# LcsNodes-Extension-4x4-Occ-Detect-B_02_0.net
KiCad netlist of a schematic drawn in EasyEDA
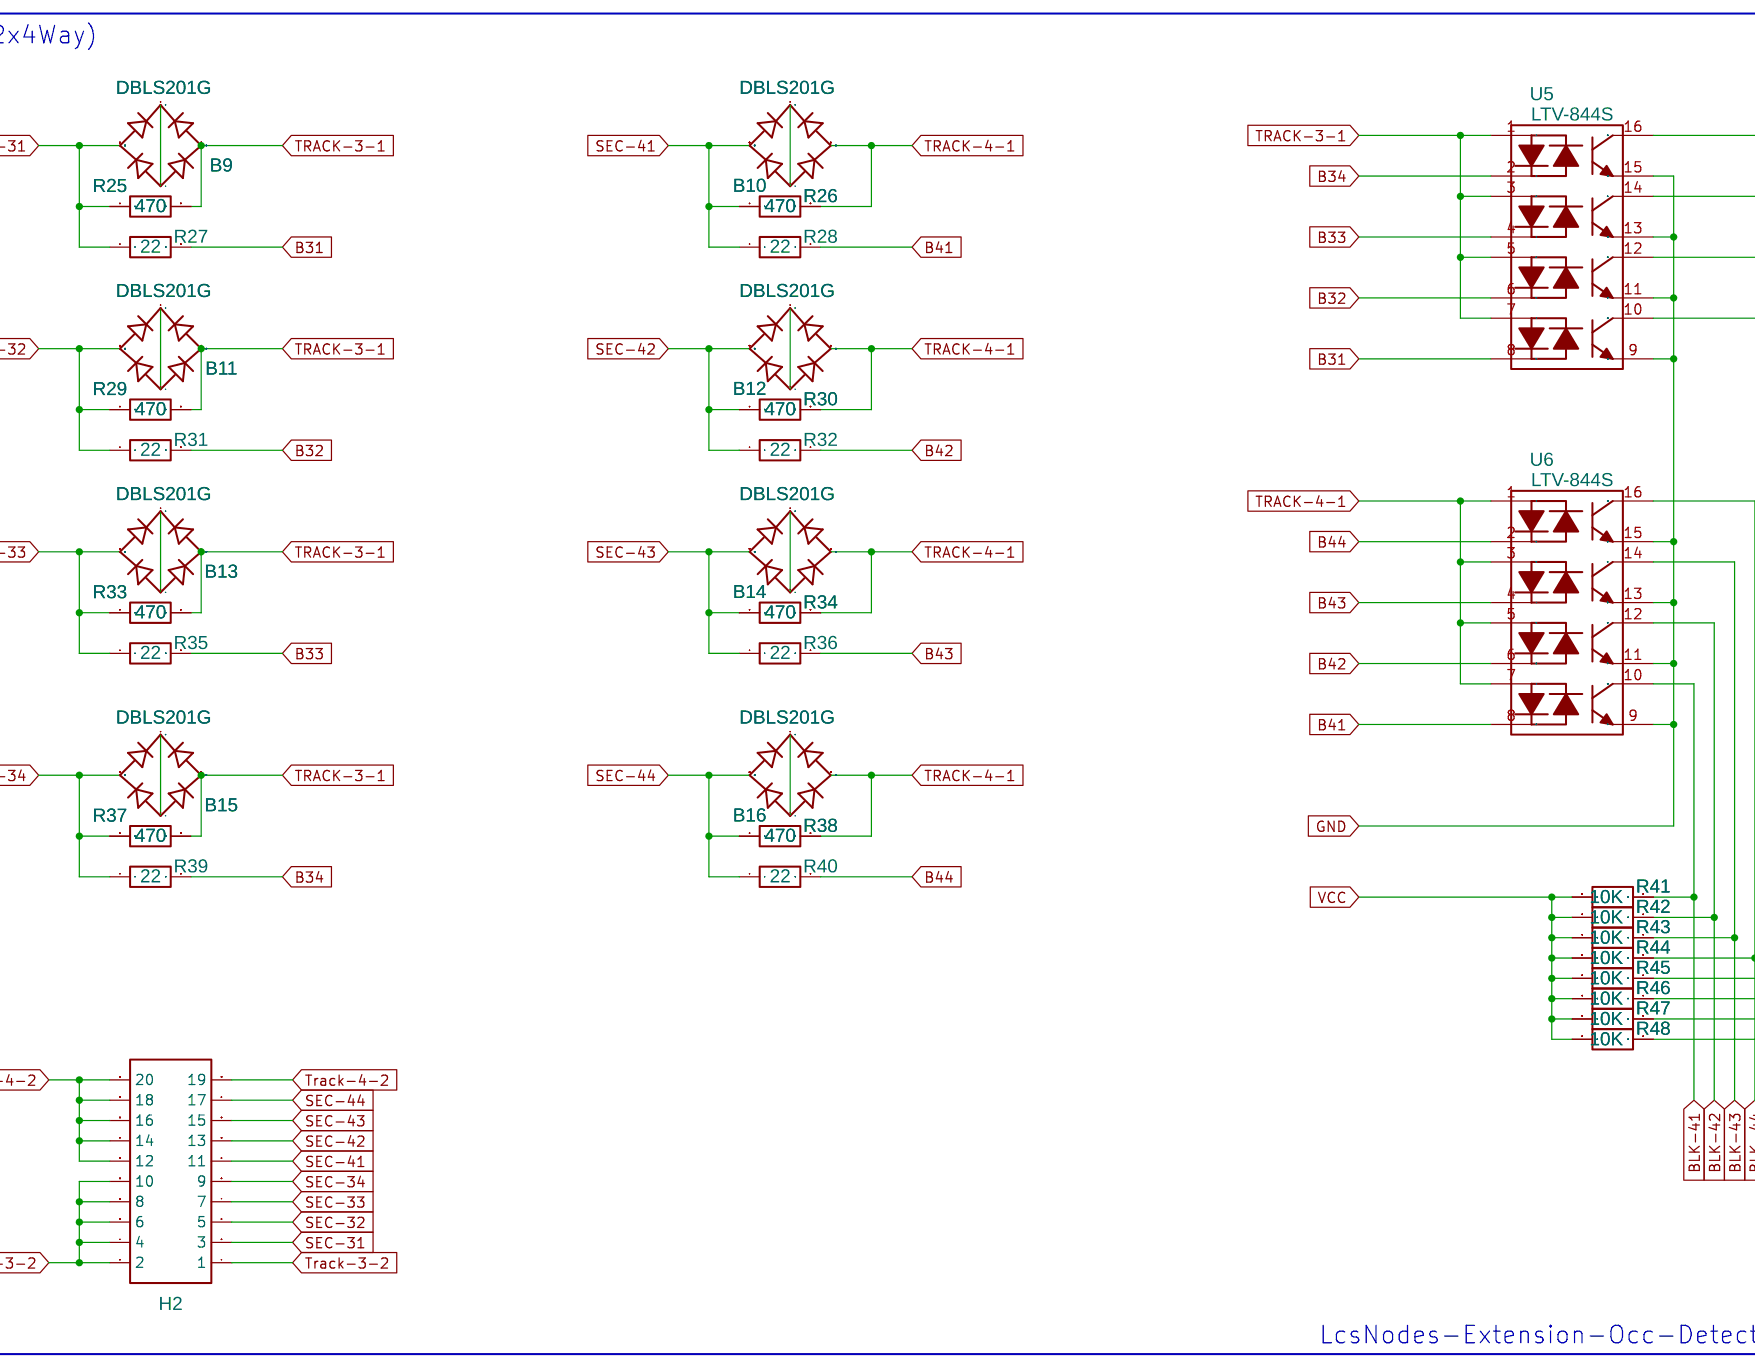
[diagram p0: Sensor-Array-2]
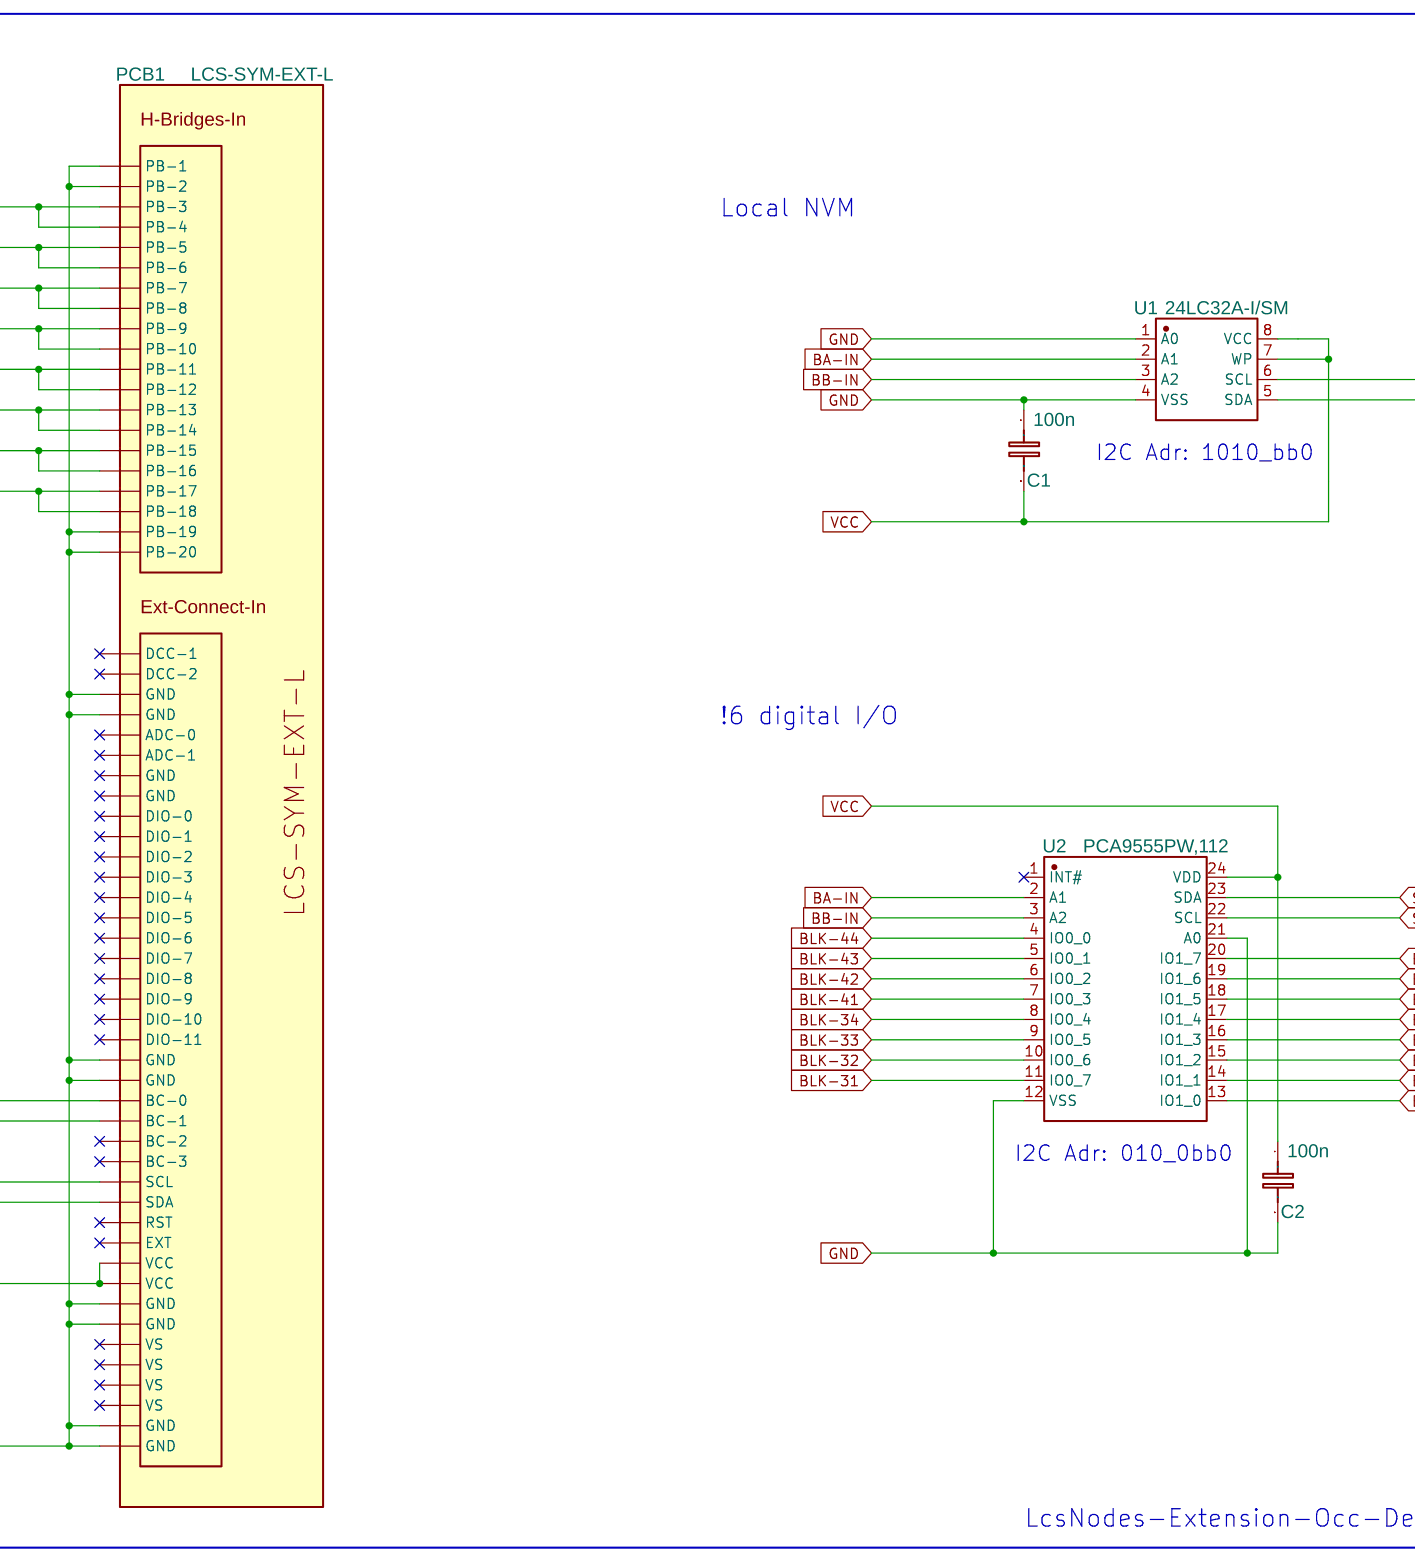
[diagram p1: Connector-and-Logic]
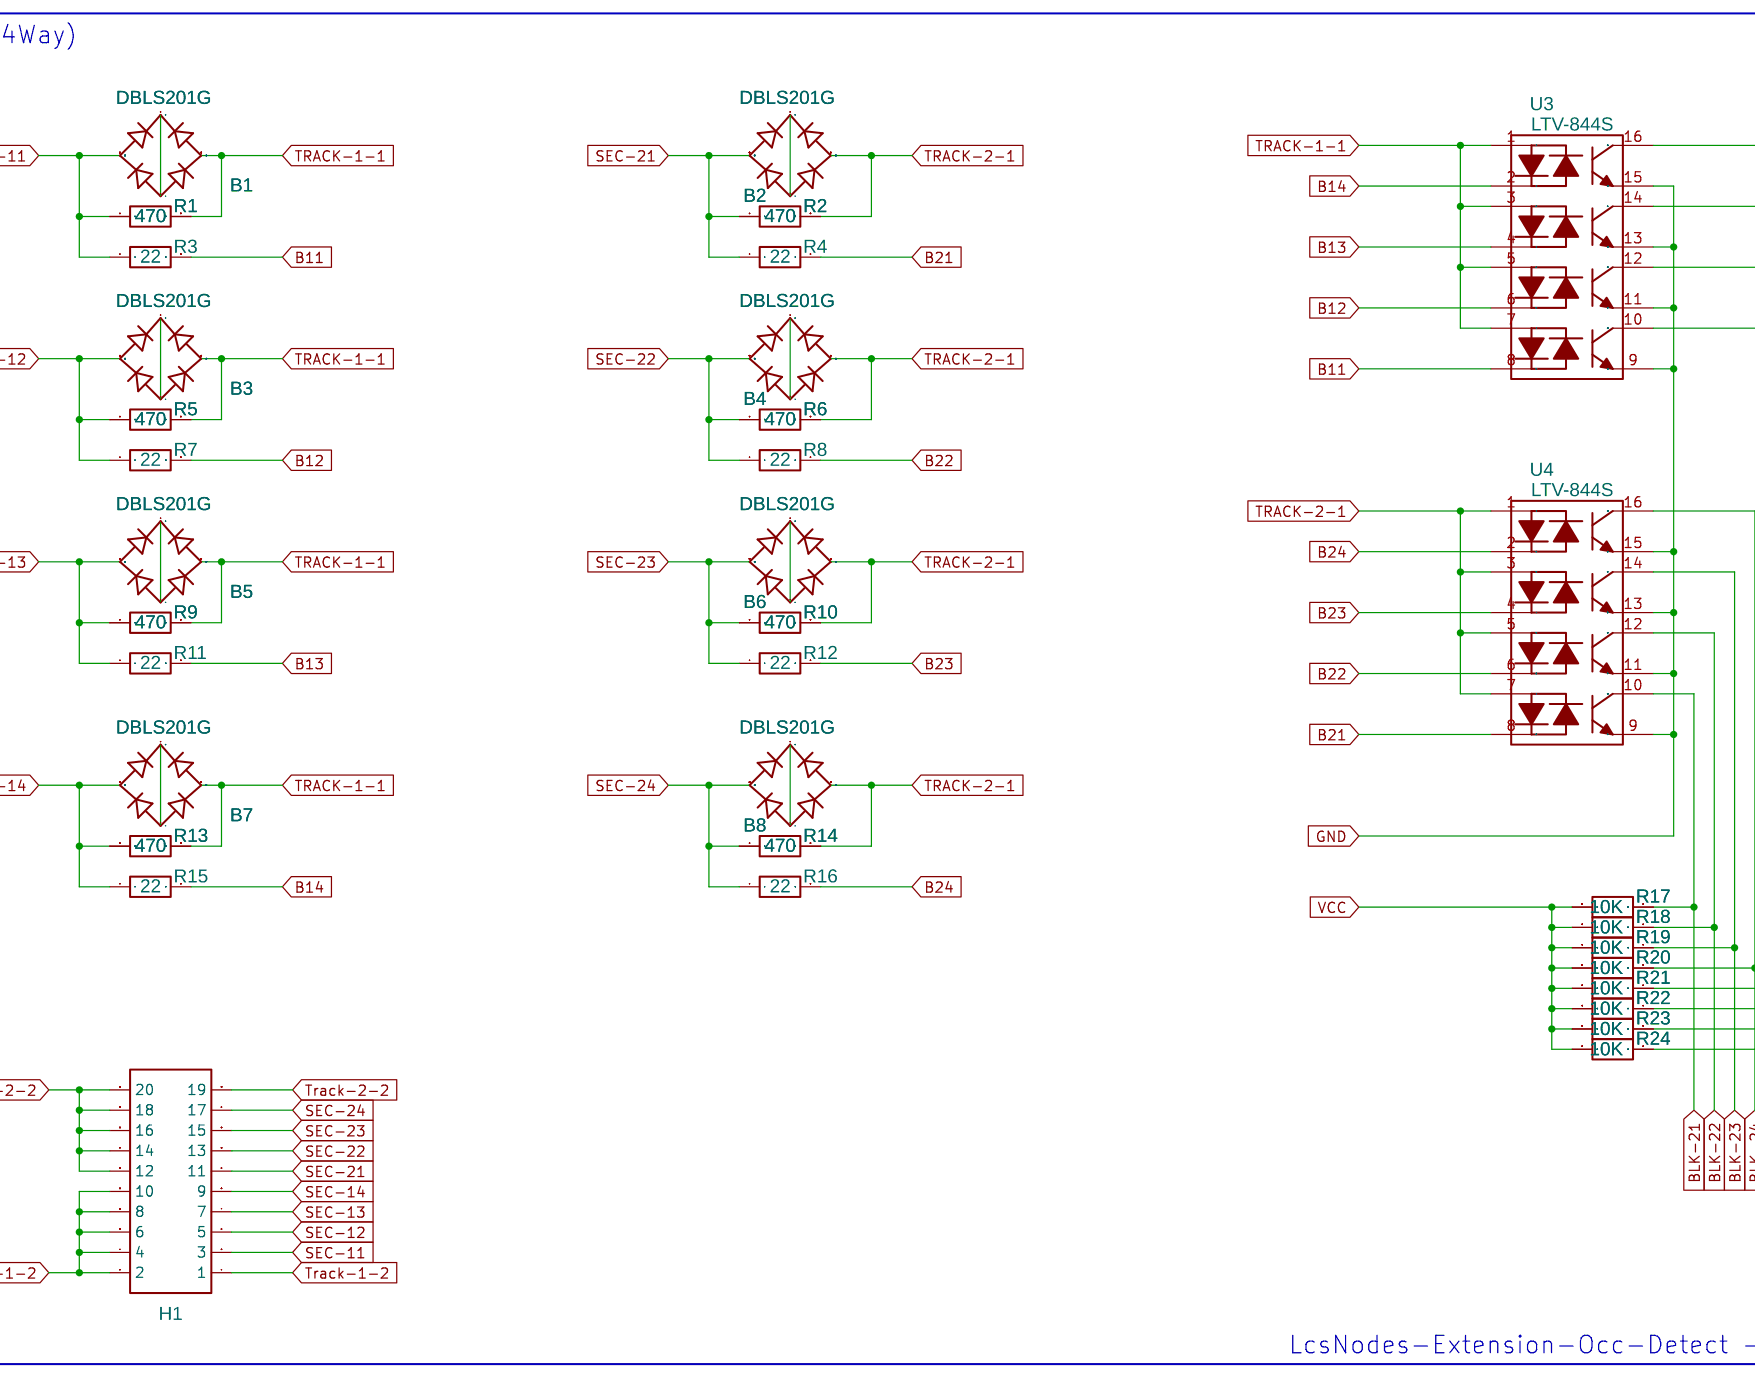
[diagram p2: Sensor-Array-1]

(export (version "E")
  (design (tool "Eeschema 10.0.6"))
  (components
    (comp (ref "B9") (value "DBLS201G") (libsource (lib "") (part "DBLS201G_1")))
    (comp (ref "B10") (value "DBLS201G") (libsource (lib "") (part "DBLS201G")))
    (comp (ref "B11") (value "DBLS201G") (libsource (lib "") (part "DBLS201G_1")))
    (comp (ref "B12") (value "DBLS201G") (libsource (lib "") (part "DBLS201G")))
    (comp (ref "B13") (value "DBLS201G") (libsource (lib "") (part "DBLS201G_1")))
    (comp (ref "B14") (value "DBLS201G") (libsource (lib "") (part "DBLS201G")))
    (comp (ref "B15") (value "DBLS201G") (libsource (lib "") (part "DBLS201G_1")))
    (comp (ref "B16") (value "DBLS201G") (libsource (lib "") (part "DBLS201G")))
    (comp (ref "H2") (value "HDR-F-2.54_2x10") (libsource (lib "") (part "HDR-F-2.54_2x10")))
    (comp (ref "R25") (value "470") (libsource (lib "") (part "R_AXIAL-0.3_EU_1")))
    (comp (ref "R26") (value "470") (libsource (lib "") (part "R_AXIAL-0.3_EU_1")))
    (comp (ref "R27") (value "22") (libsource (lib "") (part "R_AXIAL-0.3_EU_1")))
    (comp (ref "R28") (value "22") (libsource (lib "") (part "R_AXIAL-0.3_EU_1")))
    (comp (ref "R29") (value "470") (libsource (lib "") (part "R_AXIAL-0.3_EU_1")))
    (comp (ref "R30") (value "470") (libsource (lib "") (part "R_AXIAL-0.3_EU_1")))
    (comp (ref "R31") (value "22") (libsource (lib "") (part "R_AXIAL-0.3_EU_1")))
    (comp (ref "R32") (value "22") (libsource (lib "") (part "R_AXIAL-0.3_EU_1")))
    (comp (ref "R33") (value "470") (libsource (lib "") (part "R_AXIAL-0.3_EU_1")))
    (comp (ref "R34") (value "470") (libsource (lib "") (part "R_AXIAL-0.3_EU_1")))
    (comp (ref "R35") (value "22") (libsource (lib "") (part "R_AXIAL-0.3_EU_1")))
    (comp (ref "R36") (value "22") (libsource (lib "") (part "R_AXIAL-0.3_EU_1")))
    (comp (ref "R37") (value "470") (libsource (lib "") (part "R_AXIAL-0.3_EU_1")))
    (comp (ref "R38") (value "470") (libsource (lib "") (part "R_AXIAL-0.3_EU_1")))
    (comp (ref "R39") (value "22") (libsource (lib "") (part "R_AXIAL-0.3_EU_1")))
    (comp (ref "R40") (value "22") (libsource (lib "") (part "R_AXIAL-0.3_EU_1")))
    (comp (ref "R41") (value "10K") (libsource (lib "") (part "R_AXIAL-0.3_EU")))
    (comp (ref "R42") (value "10K") (libsource (lib "") (part "R_AXIAL-0.3_EU")))
    (comp (ref "R43") (value "10K") (libsource (lib "") (part "R_AXIAL-0.3_EU")))
    (comp (ref "R44") (value "10K") (libsource (lib "") (part "R_AXIAL-0.3_EU")))
    (comp (ref "R45") (value "10K") (libsource (lib "") (part "R_AXIAL-0.3_EU")))
    (comp (ref "R46") (value "10K") (libsource (lib "") (part "R_AXIAL-0.3_EU")))
    (comp (ref "R47") (value "10K") (libsource (lib "") (part "R_AXIAL-0.3_EU")))
    (comp (ref "R48") (value "10K") (libsource (lib "") (part "R_AXIAL-0.3_EU")))
    (comp (ref "U5")
      (value "LTV-844S")
      (fields (field (name "Manufacturer") "LITEON(台湾光宝)"))
      (libsource (lib "") (part "LTV-844S"))
    )
    (comp (ref "U6")
      (value "LTV-844S")
      (fields (field (name "Manufacturer") "LITEON(台湾光宝)"))
      (libsource (lib "") (part "LTV-844S"))
    )
    (comp (ref "C1") (value "100n") (libsource (lib "") (part "C_0603_EU")))
    (comp (ref "C2") (value "100n") (libsource (lib "") (part "C_0603_EU_1")))
    (comp (ref "PCB1") (value "LCS-SYM-EXT-L") (libsource (lib "") (part "LCS-SYM-EXT-L")))
    (comp (ref "U1")
      (value "24LC32A-I/SM")
      (fields (field (name "Manufacturer") "MICROCHIP(美国微芯)"))
      (libsource (lib "") (part "24LC32A-I/SM"))
    )
    (comp (ref "U2")
      (value "PCA9555PW,112")
      (fields (field (name "Manufacturer") "NXP(恩智浦)"))
      (libsource (lib "") (part "PCA9555PW,112"))
    )
    (comp (ref "B1") (value "DBLS201G") (libsource (lib "") (part "DBLS201G_1")))
    (comp (ref "B2") (value "DBLS201G") (libsource (lib "") (part "DBLS201G")))
    (comp (ref "B3") (value "DBLS201G") (libsource (lib "") (part "DBLS201G_1")))
    (comp (ref "B4") (value "DBLS201G") (libsource (lib "") (part "DBLS201G")))
    (comp (ref "B5") (value "DBLS201G") (libsource (lib "") (part "DBLS201G_1")))
    (comp (ref "B6") (value "DBLS201G") (libsource (lib "") (part "DBLS201G")))
    (comp (ref "B7") (value "DBLS201G") (libsource (lib "") (part "DBLS201G_1")))
    (comp (ref "B8") (value "DBLS201G") (libsource (lib "") (part "DBLS201G")))
    (comp (ref "H1") (value "HDR-F-2.54_2x10") (libsource (lib "") (part "HDR-F-2.54_2x10")))
    (comp (ref "R1") (value "470") (libsource (lib "") (part "R_AXIAL-0.3_EU")))
    (comp (ref "R2") (value "470") (libsource (lib "") (part "R_AXIAL-0.3_EU")))
    (comp (ref "R3") (value "22") (libsource (lib "") (part "R_AXIAL-0.3_EU")))
    (comp (ref "R4") (value "22") (libsource (lib "") (part "R_AXIAL-0.3_EU")))
    (comp (ref "R5") (value "470") (libsource (lib "") (part "R_AXIAL-0.3_EU")))
    (comp (ref "R6") (value "470") (libsource (lib "") (part "R_AXIAL-0.3_EU")))
    (comp (ref "R7") (value "22") (libsource (lib "") (part "R_AXIAL-0.3_EU")))
    (comp (ref "R8") (value "22") (libsource (lib "") (part "R_AXIAL-0.3_EU")))
    (comp (ref "R9") (value "470") (libsource (lib "") (part "R_AXIAL-0.3_EU")))
    (comp (ref "R10") (value "470") (libsource (lib "") (part "R_AXIAL-0.3_EU")))
    (comp (ref "R11") (value "22") (libsource (lib "") (part "R_AXIAL-0.3_EU")))
    (comp (ref "R12") (value "22") (libsource (lib "") (part "R_AXIAL-0.3_EU")))
    (comp (ref "R13") (value "470") (libsource (lib "") (part "R_AXIAL-0.3_EU")))
    (comp (ref "R14") (value "470") (libsource (lib "") (part "R_AXIAL-0.3_EU")))
    (comp (ref "R15") (value "22") (libsource (lib "") (part "R_AXIAL-0.3_EU")))
    (comp (ref "R16") (value "22") (libsource (lib "") (part "R_AXIAL-0.3_EU")))
    (comp (ref "R17") (value "10K") (libsource (lib "") (part "R_AXIAL-0.3_EU_1")))
    (comp (ref "R18") (value "10K") (libsource (lib "") (part "R_AXIAL-0.3_EU_1")))
    (comp (ref "R19") (value "10K") (libsource (lib "") (part "R_AXIAL-0.3_EU_1")))
    (comp (ref "R20") (value "10K") (libsource (lib "") (part "R_AXIAL-0.3_EU_1")))
    (comp (ref "R21") (value "10K") (libsource (lib "") (part "R_AXIAL-0.3_EU_1")))
    (comp (ref "R22") (value "10K") (libsource (lib "") (part "R_AXIAL-0.3_EU_1")))
    (comp (ref "R23") (value "10K") (libsource (lib "") (part "R_AXIAL-0.3_EU_1")))
    (comp (ref "R24") (value "10K") (libsource (lib "") (part "R_AXIAL-0.3_EU_1")))
    (comp (ref "U3")
      (value "LTV-844S")
      (fields (field (name "Manufacturer") "LITEON(台湾光宝)"))
      (libsource (lib "") (part "LTV-844S"))
    )
    (comp (ref "U4")
      (value "LTV-844S")
      (fields (field (name "Manufacturer") "LITEON(台湾光宝)"))
      (libsource (lib "") (part "LTV-844S"))
    )
  )
  (nets
    (net (code "1") (name "B11") (class "Default")
      (node (ref "R3") (pin "2") (pinfunction "2_2") (pintype "unspecified"))
      (node (ref "U3") (pin "8") (pinfunction "8_8") (pintype "unspecified"))
    )
    (net (code "2") (name "B12") (class "Default")
      (node (ref "R7") (pin "2") (pinfunction "2_2") (pintype "unspecified"))
      (node (ref "U3") (pin "6") (pinfunction "6_6") (pintype "unspecified"))
    )
    (net (code "3") (name "B13") (class "Default")
      (node (ref "R11") (pin "2") (pinfunction "2_2") (pintype "unspecified"))
      (node (ref "U3") (pin "4") (pinfunction "4_4") (pintype "unspecified"))
    )
    (net (code "4") (name "B14") (class "Default")
      (node (ref "R15") (pin "2") (pinfunction "2_2") (pintype "unspecified"))
      (node (ref "U3") (pin "2") (pinfunction "2_2") (pintype "unspecified"))
    )
    (net (code "5") (name "B21") (class "Default")
      (node (ref "R4") (pin "2") (pinfunction "2_2") (pintype "unspecified"))
      (node (ref "U4") (pin "8") (pinfunction "8_8") (pintype "unspecified"))
    )
    (net (code "6") (name "B22") (class "Default")
      (node (ref "R8") (pin "2") (pinfunction "2_2") (pintype "unspecified"))
      (node (ref "U4") (pin "6") (pinfunction "6_6") (pintype "unspecified"))
    )
    (net (code "7") (name "B23") (class "Default")
      (node (ref "R12") (pin "2") (pinfunction "2_2") (pintype "unspecified"))
      (node (ref "U4") (pin "4") (pinfunction "4_4") (pintype "unspecified"))
    )
    (net (code "8") (name "B24") (class "Default")
      (node (ref "R16") (pin "2") (pinfunction "2_2") (pintype "unspecified"))
      (node (ref "U4") (pin "2") (pinfunction "2_2") (pintype "unspecified"))
    )
    (net (code "9") (name "B31") (class "Default")
      (node (ref "R27") (pin "2") (pinfunction "2_2") (pintype "unspecified"))
      (node (ref "U5") (pin "8") (pinfunction "8_8") (pintype "unspecified"))
    )
    (net (code "10") (name "B32") (class "Default")
      (node (ref "R31") (pin "2") (pinfunction "2_2") (pintype "unspecified"))
      (node (ref "U5") (pin "6") (pinfunction "6_6") (pintype "unspecified"))
    )
    (net (code "11") (name "B33") (class "Default")
      (node (ref "R35") (pin "2") (pinfunction "2_2") (pintype "unspecified"))
      (node (ref "U5") (pin "4") (pinfunction "4_4") (pintype "unspecified"))
    )
    (net (code "12") (name "B34") (class "Default")
      (node (ref "R39") (pin "2") (pinfunction "2_2") (pintype "unspecified"))
      (node (ref "U5") (pin "2") (pinfunction "2_2") (pintype "unspecified"))
    )
    (net (code "13") (name "B41") (class "Default")
      (node (ref "R28") (pin "2") (pinfunction "2_2") (pintype "unspecified"))
      (node (ref "U6") (pin "8") (pinfunction "8_8") (pintype "unspecified"))
    )
    (net (code "14") (name "B42") (class "Default")
      (node (ref "R32") (pin "2") (pinfunction "2_2") (pintype "unspecified"))
      (node (ref "U6") (pin "6") (pinfunction "6_6") (pintype "unspecified"))
    )
    (net (code "15") (name "B43") (class "Default")
      (node (ref "R36") (pin "2") (pinfunction "2_2") (pintype "unspecified"))
      (node (ref "U6") (pin "4") (pinfunction "4_4") (pintype "unspecified"))
    )
    (net (code "16") (name "B44") (class "Default")
      (node (ref "R40") (pin "2") (pinfunction "2_2") (pintype "unspecified"))
      (node (ref "U6") (pin "2") (pinfunction "2_2") (pintype "unspecified"))
    )
    (net (code "17") (name "BA-IN") (class "Default")
      (node (ref "PCB1") (pin "82") (pinfunction "BC-0_82") (pintype "unspecified"))
      (node (ref "U1") (pin "2") (pinfunction "A1_2") (pintype "unspecified"))
      (node (ref "U2") (pin "2") (pinfunction "A1_2") (pintype "unspecified"))
    )
    (net (code "18") (name "BB-IN") (class "Default")
      (node (ref "PCB1") (pin "83") (pinfunction "BC-1_83") (pintype "unspecified"))
      (node (ref "U1") (pin "3") (pinfunction "A2_3") (pintype "unspecified"))
      (node (ref "U2") (pin "3") (pinfunction "A2_3") (pintype "unspecified"))
    )
    (net (code "19") (name "BLK-11") (class "Default")
      (node (ref "R21") (pin "1") (pinfunction "1_1") (pintype "unspecified"))
      (node (ref "U2") (pin "20") (pinfunction "IO1_7_20") (pintype "unspecified"))
      (node (ref "U3") (pin "10") (pinfunction "10_10") (pintype "unspecified"))
    )
    (net (code "20") (name "BLK-12") (class "Default")
      (node (ref "R22") (pin "1") (pinfunction "1_1") (pintype "unspecified"))
      (node (ref "U2") (pin "19") (pinfunction "IO1_6_19") (pintype "unspecified"))
      (node (ref "U3") (pin "12") (pinfunction "12_12") (pintype "unspecified"))
    )
    (net (code "21") (name "BLK-13") (class "Default")
      (node (ref "R23") (pin "1") (pinfunction "1_1") (pintype "unspecified"))
      (node (ref "U2") (pin "18") (pinfunction "IO1_5_18") (pintype "unspecified"))
      (node (ref "U3") (pin "14") (pinfunction "14_14") (pintype "unspecified"))
    )
    (net (code "22") (name "BLK-14") (class "Default")
      (node (ref "R24") (pin "1") (pinfunction "1_1") (pintype "unspecified"))
      (node (ref "U2") (pin "17") (pinfunction "IO1_4_17") (pintype "unspecified"))
      (node (ref "U3") (pin "16") (pinfunction "16_16") (pintype "unspecified"))
    )
    (net (code "23") (name "BLK-21") (class "Default")
      (node (ref "R17") (pin "1") (pinfunction "1_1") (pintype "unspecified"))
      (node (ref "U2") (pin "16") (pinfunction "IO1_3_16") (pintype "unspecified"))
      (node (ref "U4") (pin "10") (pinfunction "10_10") (pintype "unspecified"))
    )
    (net (code "24") (name "BLK-22") (class "Default")
      (node (ref "R18") (pin "1") (pinfunction "1_1") (pintype "unspecified"))
      (node (ref "U2") (pin "15") (pinfunction "IO1_2_15") (pintype "unspecified"))
      (node (ref "U4") (pin "12") (pinfunction "12_12") (pintype "unspecified"))
    )
    (net (code "25") (name "BLK-23") (class "Default")
      (node (ref "R19") (pin "1") (pinfunction "1_1") (pintype "unspecified"))
      (node (ref "U2") (pin "14") (pinfunction "IO1_1_14") (pintype "unspecified"))
      (node (ref "U4") (pin "14") (pinfunction "14_14") (pintype "unspecified"))
    )
    (net (code "26") (name "BLK-24") (class "Default")
      (node (ref "R20") (pin "1") (pinfunction "1_1") (pintype "unspecified"))
      (node (ref "U2") (pin "13") (pinfunction "IO1_0_13") (pintype "unspecified"))
      (node (ref "U4") (pin "16") (pinfunction "16_16") (pintype "unspecified"))
    )
    (net (code "27") (name "BLK-31") (class "Default")
      (node (ref "R45") (pin "1") (pinfunction "1_1") (pintype "unspecified"))
      (node (ref "U2") (pin "11") (pinfunction "IO0_7_11") (pintype "unspecified"))
      (node (ref "U5") (pin "10") (pinfunction "10_10") (pintype "unspecified"))
    )
    (net (code "28") (name "BLK-32") (class "Default")
      (node (ref "R46") (pin "1") (pinfunction "1_1") (pintype "unspecified"))
      (node (ref "U2") (pin "10") (pinfunction "IO0_6_10") (pintype "unspecified"))
      (node (ref "U5") (pin "12") (pinfunction "12_12") (pintype "unspecified"))
    )
    (net (code "29") (name "BLK-33") (class "Default")
      (node (ref "R47") (pin "1") (pinfunction "1_1") (pintype "unspecified"))
      (node (ref "U2") (pin "9") (pinfunction "IO0_5_9") (pintype "unspecified"))
      (node (ref "U5") (pin "14") (pinfunction "14_14") (pintype "unspecified"))
    )
    (net (code "30") (name "BLK-34") (class "Default")
      (node (ref "R48") (pin "1") (pinfunction "1_1") (pintype "unspecified"))
      (node (ref "U2") (pin "8") (pinfunction "IO0_4_8") (pintype "unspecified"))
      (node (ref "U5") (pin "16") (pinfunction "16_16") (pintype "unspecified"))
    )
    (net (code "31") (name "BLK-41") (class "Default")
      (node (ref "R41") (pin "1") (pinfunction "1_1") (pintype "unspecified"))
      (node (ref "U2") (pin "7") (pinfunction "IO0_3_7") (pintype "unspecified"))
      (node (ref "U6") (pin "10") (pinfunction "10_10") (pintype "unspecified"))
    )
    (net (code "32") (name "BLK-42") (class "Default")
      (node (ref "R42") (pin "1") (pinfunction "1_1") (pintype "unspecified"))
      (node (ref "U2") (pin "6") (pinfunction "IO0_2_6") (pintype "unspecified"))
      (node (ref "U6") (pin "12") (pinfunction "12_12") (pintype "unspecified"))
    )
    (net (code "33") (name "BLK-43") (class "Default")
      (node (ref "R43") (pin "1") (pinfunction "1_1") (pintype "unspecified"))
      (node (ref "U2") (pin "5") (pinfunction "IO0_1_5") (pintype "unspecified"))
      (node (ref "U6") (pin "14") (pinfunction "14_14") (pintype "unspecified"))
    )
    (net (code "34") (name "BLK-44") (class "Default")
      (node (ref "R44") (pin "1") (pinfunction "1_1") (pintype "unspecified"))
      (node (ref "U2") (pin "4") (pinfunction "IO0_0_4") (pintype "unspecified"))
      (node (ref "U6") (pin "16") (pinfunction "16_16") (pintype "unspecified"))
    )
    (net (code "35") (name "GND") (class "Default")
      (node (ref "C1") (pin "1") (pinfunction "1_1") (pintype "unspecified"))
      (node (ref "C2") (pin "2") (pinfunction "2_2") (pintype "unspecified"))
      (node (ref "PCB1") (pin "30") (pinfunction "PB-1_30") (pintype "unspecified"))
      (node (ref "PCB1") (pin "31") (pinfunction "PB-2_31") (pintype "unspecified"))
      (node (ref "PCB1") (pin "48") (pinfunction "PB-19_48") (pintype "unspecified"))
      (node (ref "PCB1") (pin "49") (pinfunction "PB-20_49") (pintype "unspecified"))
      (node (ref "PCB1") (pin "62") (pinfunction "GND_62") (pintype "unspecified"))
      (node (ref "PCB1") (pin "63") (pinfunction "GND_63") (pintype "unspecified"))
      (node (ref "PCB1") (pin "80") (pinfunction "GND_80") (pintype "unspecified"))
      (node (ref "PCB1") (pin "81") (pinfunction "GND_81") (pintype "unspecified"))
      (node (ref "PCB1") (pin "92") (pinfunction "GND_92") (pintype "unspecified"))
      (node (ref "PCB1") (pin "93") (pinfunction "GND_93") (pintype "unspecified"))
      (node (ref "PCB1") (pin "98") (pinfunction "GND_98") (pintype "unspecified"))
      (node (ref "PCB1") (pin "99") (pinfunction "GND_99") (pintype "unspecified"))
      (node (ref "U1") (pin "1") (pinfunction "A0_1") (pintype "unspecified"))
      (node (ref "U1") (pin "4") (pinfunction "VSS_4") (pintype "unspecified"))
      (node (ref "U2") (pin "12") (pinfunction "VSS_12") (pintype "unspecified"))
      (node (ref "U2") (pin "21") (pinfunction "A0_21") (pintype "unspecified"))
      (node (ref "U3") (pin "11") (pinfunction "11_11") (pintype "unspecified"))
      (node (ref "U3") (pin "13") (pinfunction "13_13") (pintype "unspecified"))
      (node (ref "U3") (pin "15") (pinfunction "15_15") (pintype "unspecified"))
      (node (ref "U3") (pin "9") (pinfunction "9_9") (pintype "unspecified"))
      (node (ref "U4") (pin "11") (pinfunction "11_11") (pintype "unspecified"))
      (node (ref "U4") (pin "13") (pinfunction "13_13") (pintype "unspecified"))
      (node (ref "U4") (pin "15") (pinfunction "15_15") (pintype "unspecified"))
      (node (ref "U4") (pin "9") (pinfunction "9_9") (pintype "unspecified"))
      (node (ref "U5") (pin "11") (pinfunction "11_11") (pintype "unspecified"))
      (node (ref "U5") (pin "13") (pinfunction "13_13") (pintype "unspecified"))
      (node (ref "U5") (pin "15") (pinfunction "15_15") (pintype "unspecified"))
      (node (ref "U5") (pin "9") (pinfunction "9_9") (pintype "unspecified"))
      (node (ref "U6") (pin "11") (pinfunction "11_11") (pintype "unspecified"))
      (node (ref "U6") (pin "13") (pinfunction "13_13") (pintype "unspecified"))
      (node (ref "U6") (pin "15") (pinfunction "15_15") (pintype "unspecified"))
      (node (ref "U6") (pin "9") (pinfunction "9_9") (pintype "unspecified"))
    )
    (net (code "36") (name "Net-(B1-Pad+)") (class "Default")
      (node (ref "B1") (pin "+") (pinfunction "+_+") (pintype "unspecified"))
      (node (ref "B1") (pin "-") (pinfunction "-_-") (pintype "unspecified"))
    )
    (net (code "37") (name "Net-(B2-Pad+)") (class "Default")
      (node (ref "B2") (pin "+") (pinfunction "+_+") (pintype "unspecified"))
      (node (ref "B2") (pin "-") (pinfunction "-_-") (pintype "unspecified"))
    )
    (net (code "38") (name "Net-(B3-Pad+)") (class "Default")
      (node (ref "B3") (pin "+") (pinfunction "+_+") (pintype "unspecified"))
      (node (ref "B3") (pin "-") (pinfunction "-_-") (pintype "unspecified"))
    )
    (net (code "39") (name "Net-(B4-Pad+)") (class "Default")
      (node (ref "B4") (pin "+") (pinfunction "+_+") (pintype "unspecified"))
      (node (ref "B4") (pin "-") (pinfunction "-_-") (pintype "unspecified"))
    )
    (net (code "40") (name "Net-(B5-Pad+)") (class "Default")
      (node (ref "B5") (pin "+") (pinfunction "+_+") (pintype "unspecified"))
      (node (ref "B5") (pin "-") (pinfunction "-_-") (pintype "unspecified"))
    )
    (net (code "41") (name "Net-(B6-Pad+)") (class "Default")
      (node (ref "B6") (pin "+") (pinfunction "+_+") (pintype "unspecified"))
      (node (ref "B6") (pin "-") (pinfunction "-_-") (pintype "unspecified"))
    )
    (net (code "42") (name "Net-(B7-Pad+)") (class "Default")
      (node (ref "B7") (pin "+") (pinfunction "+_+") (pintype "unspecified"))
      (node (ref "B7") (pin "-") (pinfunction "-_-") (pintype "unspecified"))
    )
    (net (code "43") (name "Net-(B8-Pad+)") (class "Default")
      (node (ref "B8") (pin "+") (pinfunction "+_+") (pintype "unspecified"))
      (node (ref "B8") (pin "-") (pinfunction "-_-") (pintype "unspecified"))
    )
    (net (code "44") (name "Net-(B9-Pad+)") (class "Default")
      (node (ref "B9") (pin "+") (pinfunction "+_+") (pintype "unspecified"))
      (node (ref "B9") (pin "-") (pinfunction "-_-") (pintype "unspecified"))
    )
    (net (code "45") (name "Net-(B10-Pad+)") (class "Default")
      (node (ref "B10") (pin "+") (pinfunction "+_+") (pintype "unspecified"))
      (node (ref "B10") (pin "-") (pinfunction "-_-") (pintype "unspecified"))
    )
    (net (code "46") (name "Net-(B11-Pad+)") (class "Default")
      (node (ref "B11") (pin "+") (pinfunction "+_+") (pintype "unspecified"))
      (node (ref "B11") (pin "-") (pinfunction "-_-") (pintype "unspecified"))
    )
    (net (code "47") (name "Net-(B12-Pad+)") (class "Default")
      (node (ref "B12") (pin "+") (pinfunction "+_+") (pintype "unspecified"))
      (node (ref "B12") (pin "-") (pinfunction "-_-") (pintype "unspecified"))
    )
    (net (code "48") (name "Net-(B13-Pad+)") (class "Default")
      (node (ref "B13") (pin "+") (pinfunction "+_+") (pintype "unspecified"))
      (node (ref "B13") (pin "-") (pinfunction "-_-") (pintype "unspecified"))
    )
    (net (code "49") (name "Net-(B14-Pad+)") (class "Default")
      (node (ref "B14") (pin "+") (pinfunction "+_+") (pintype "unspecified"))
      (node (ref "B14") (pin "-") (pinfunction "-_-") (pintype "unspecified"))
    )
    (net (code "50") (name "Net-(B15-Pad+)") (class "Default")
      (node (ref "B15") (pin "+") (pinfunction "+_+") (pintype "unspecified"))
      (node (ref "B15") (pin "-") (pinfunction "-_-") (pintype "unspecified"))
    )
    (net (code "51") (name "Net-(B16-Pad+)") (class "Default")
      (node (ref "B16") (pin "+") (pinfunction "+_+") (pintype "unspecified"))
      (node (ref "B16") (pin "-") (pinfunction "-_-") (pintype "unspecified"))
    )
    (net (code "52") (name "SCL") (class "Default")
      (node (ref "PCB1") (pin "86") (pinfunction "SCL_86") (pintype "unspecified"))
      (node (ref "U1") (pin "6") (pinfunction "SCL_6") (pintype "unspecified"))
      (node (ref "U2") (pin "22") (pinfunction "SCL_22") (pintype "unspecified"))
    )
    (net (code "53") (name "SDA") (class "Default")
      (node (ref "PCB1") (pin "87") (pinfunction "SDA_87") (pintype "unspecified"))
      (node (ref "U1") (pin "5") (pinfunction "SDA_5") (pintype "unspecified"))
      (node (ref "U2") (pin "23") (pinfunction "SDA_23") (pintype "unspecified"))
    )
    (net (code "54") (name "SEC-11") (class "Default")
      (node (ref "B1") (pin "AC1") (pinfunction "AC1_AC1") (pintype "unspecified"))
      (node (ref "H1") (pin "3") (pinfunction "3_3") (pintype "input"))
      (node (ref "R1") (pin "1") (pinfunction "1_1") (pintype "unspecified"))
      (node (ref "R3") (pin "1") (pinfunction "1_1") (pintype "unspecified"))
    )
    (net (code "55") (name "SEC-12") (class "Default")
      (node (ref "B3") (pin "AC1") (pinfunction "AC1_AC1") (pintype "unspecified"))
      (node (ref "H1") (pin "5") (pinfunction "5_5") (pintype "input"))
      (node (ref "R5") (pin "1") (pinfunction "1_1") (pintype "unspecified"))
      (node (ref "R7") (pin "1") (pinfunction "1_1") (pintype "unspecified"))
    )
    (net (code "56") (name "SEC-13") (class "Default")
      (node (ref "B5") (pin "AC1") (pinfunction "AC1_AC1") (pintype "unspecified"))
      (node (ref "H1") (pin "7") (pinfunction "7_7") (pintype "input"))
      (node (ref "R11") (pin "1") (pinfunction "1_1") (pintype "unspecified"))
      (node (ref "R9") (pin "1") (pinfunction "1_1") (pintype "unspecified"))
    )
    (net (code "57") (name "SEC-14") (class "Default")
      (node (ref "B7") (pin "AC1") (pinfunction "AC1_AC1") (pintype "unspecified"))
      (node (ref "H1") (pin "9") (pinfunction "9_9") (pintype "input"))
      (node (ref "R13") (pin "1") (pinfunction "1_1") (pintype "unspecified"))
      (node (ref "R15") (pin "1") (pinfunction "1_1") (pintype "unspecified"))
    )
    (net (code "58") (name "SEC-21") (class "Default")
      (node (ref "B2") (pin "AC2") (pinfunction "AC2_AC2") (pintype "unspecified"))
      (node (ref "H1") (pin "11") (pinfunction "11_11") (pintype "input"))
      (node (ref "R2") (pin "1") (pinfunction "1_1") (pintype "unspecified"))
      (node (ref "R4") (pin "1") (pinfunction "1_1") (pintype "unspecified"))
    )
    (net (code "59") (name "SEC-22") (class "Default")
      (node (ref "B4") (pin "AC2") (pinfunction "AC2_AC2") (pintype "unspecified"))
      (node (ref "H1") (pin "13") (pinfunction "13_13") (pintype "input"))
      (node (ref "R6") (pin "1") (pinfunction "1_1") (pintype "unspecified"))
      (node (ref "R8") (pin "1") (pinfunction "1_1") (pintype "unspecified"))
    )
    (net (code "60") (name "SEC-23") (class "Default")
      (node (ref "B6") (pin "AC2") (pinfunction "AC2_AC2") (pintype "unspecified"))
      (node (ref "H1") (pin "15") (pinfunction "15_15") (pintype "input"))
      (node (ref "R10") (pin "1") (pinfunction "1_1") (pintype "unspecified"))
      (node (ref "R12") (pin "1") (pinfunction "1_1") (pintype "unspecified"))
    )
    (net (code "61") (name "SEC-24") (class "Default")
      (node (ref "B8") (pin "AC2") (pinfunction "AC2_AC2") (pintype "unspecified"))
      (node (ref "H1") (pin "17") (pinfunction "17_17") (pintype "input"))
      (node (ref "R14") (pin "1") (pinfunction "1_1") (pintype "unspecified"))
      (node (ref "R16") (pin "1") (pinfunction "1_1") (pintype "unspecified"))
    )
    (net (code "62") (name "SEC-31") (class "Default")
      (node (ref "B9") (pin "AC1") (pinfunction "AC1_AC1") (pintype "unspecified"))
      (node (ref "H2") (pin "3") (pinfunction "3_3") (pintype "input"))
      (node (ref "R25") (pin "1") (pinfunction "1_1") (pintype "unspecified"))
      (node (ref "R27") (pin "1") (pinfunction "1_1") (pintype "unspecified"))
    )
    (net (code "63") (name "SEC-32") (class "Default")
      (node (ref "B11") (pin "AC1") (pinfunction "AC1_AC1") (pintype "unspecified"))
      (node (ref "H2") (pin "5") (pinfunction "5_5") (pintype "input"))
      (node (ref "R29") (pin "1") (pinfunction "1_1") (pintype "unspecified"))
      (node (ref "R31") (pin "1") (pinfunction "1_1") (pintype "unspecified"))
    )
    (net (code "64") (name "SEC-33") (class "Default")
      (node (ref "B13") (pin "AC1") (pinfunction "AC1_AC1") (pintype "unspecified"))
      (node (ref "H2") (pin "7") (pinfunction "7_7") (pintype "input"))
      (node (ref "R33") (pin "1") (pinfunction "1_1") (pintype "unspecified"))
      (node (ref "R35") (pin "1") (pinfunction "1_1") (pintype "unspecified"))
    )
    (net (code "65") (name "SEC-34") (class "Default")
      (node (ref "B15") (pin "AC1") (pinfunction "AC1_AC1") (pintype "unspecified"))
      (node (ref "H2") (pin "9") (pinfunction "9_9") (pintype "input"))
      (node (ref "R37") (pin "1") (pinfunction "1_1") (pintype "unspecified"))
      (node (ref "R39") (pin "1") (pinfunction "1_1") (pintype "unspecified"))
    )
    (net (code "66") (name "SEC-41") (class "Default")
      (node (ref "B10") (pin "AC2") (pinfunction "AC2_AC2") (pintype "unspecified"))
      (node (ref "H2") (pin "11") (pinfunction "11_11") (pintype "input"))
      (node (ref "R26") (pin "1") (pinfunction "1_1") (pintype "unspecified"))
      (node (ref "R28") (pin "1") (pinfunction "1_1") (pintype "unspecified"))
    )
    (net (code "67") (name "SEC-42") (class "Default")
      (node (ref "B12") (pin "AC2") (pinfunction "AC2_AC2") (pintype "unspecified"))
      (node (ref "H2") (pin "13") (pinfunction "13_13") (pintype "input"))
      (node (ref "R30") (pin "1") (pinfunction "1_1") (pintype "unspecified"))
      (node (ref "R32") (pin "1") (pinfunction "1_1") (pintype "unspecified"))
    )
    (net (code "68") (name "SEC-43") (class "Default")
      (node (ref "B14") (pin "AC2") (pinfunction "AC2_AC2") (pintype "unspecified"))
      (node (ref "H2") (pin "15") (pinfunction "15_15") (pintype "input"))
      (node (ref "R34") (pin "1") (pinfunction "1_1") (pintype "unspecified"))
      (node (ref "R36") (pin "1") (pinfunction "1_1") (pintype "unspecified"))
    )
    (net (code "69") (name "SEC-44") (class "Default")
      (node (ref "B16") (pin "AC2") (pinfunction "AC2_AC2") (pintype "unspecified"))
      (node (ref "H2") (pin "17") (pinfunction "17_17") (pintype "input"))
      (node (ref "R38") (pin "1") (pinfunction "1_1") (pintype "unspecified"))
      (node (ref "R40") (pin "1") (pinfunction "1_1") (pintype "unspecified"))
    )
    (net (code "70") (name "TRACK-1-1") (class "Default")
      (node (ref "B1") (pin "AC2") (pinfunction "AC2_AC2") (pintype "unspecified"))
      (node (ref "B3") (pin "AC2") (pinfunction "AC2_AC2") (pintype "unspecified"))
      (node (ref "B5") (pin "AC2") (pinfunction "AC2_AC2") (pintype "unspecified"))
      (node (ref "B7") (pin "AC2") (pinfunction "AC2_AC2") (pintype "unspecified"))
      (node (ref "PCB1") (pin "32") (pinfunction "PB-3_32") (pintype "unspecified"))
      (node (ref "PCB1") (pin "33") (pinfunction "PB-4_33") (pintype "unspecified"))
      (node (ref "R1") (pin "2") (pinfunction "2_2") (pintype "unspecified"))
      (node (ref "R13") (pin "2") (pinfunction "2_2") (pintype "unspecified"))
      (node (ref "R5") (pin "2") (pinfunction "2_2") (pintype "unspecified"))
      (node (ref "R9") (pin "2") (pinfunction "2_2") (pintype "unspecified"))
      (node (ref "U3") (pin "1") (pinfunction "1_1") (pintype "unspecified"))
      (node (ref "U3") (pin "3") (pinfunction "3_3") (pintype "unspecified"))
      (node (ref "U3") (pin "5") (pinfunction "5_5") (pintype "unspecified"))
      (node (ref "U3") (pin "7") (pinfunction "7_7") (pintype "unspecified"))
    )
    (net (code "71") (name "TRACK-1-2") (class "Default")
      (node (ref "PCB1") (pin "34") (pinfunction "PB-5_34") (pintype "unspecified"))
      (node (ref "PCB1") (pin "35") (pinfunction "PB-6_35") (pintype "unspecified"))
    )
    (net (code "72") (name "TRACK-2-1") (class "Default")
      (node (ref "B2") (pin "AC1") (pinfunction "AC1_AC1") (pintype "unspecified"))
      (node (ref "B4") (pin "AC1") (pinfunction "AC1_AC1") (pintype "unspecified"))
      (node (ref "B6") (pin "AC1") (pinfunction "AC1_AC1") (pintype "unspecified"))
      (node (ref "B8") (pin "AC1") (pinfunction "AC1_AC1") (pintype "unspecified"))
      (node (ref "PCB1") (pin "36") (pinfunction "PB-7_36") (pintype "unspecified"))
      (node (ref "PCB1") (pin "37") (pinfunction "PB-8_37") (pintype "unspecified"))
      (node (ref "R10") (pin "2") (pinfunction "2_2") (pintype "unspecified"))
      (node (ref "R14") (pin "2") (pinfunction "2_2") (pintype "unspecified"))
      (node (ref "R2") (pin "2") (pinfunction "2_2") (pintype "unspecified"))
      (node (ref "R6") (pin "2") (pinfunction "2_2") (pintype "unspecified"))
      (node (ref "U4") (pin "1") (pinfunction "1_1") (pintype "unspecified"))
      (node (ref "U4") (pin "3") (pinfunction "3_3") (pintype "unspecified"))
      (node (ref "U4") (pin "5") (pinfunction "5_5") (pintype "unspecified"))
      (node (ref "U4") (pin "7") (pinfunction "7_7") (pintype "unspecified"))
    )
    (net (code "73") (name "TRACK-2-2") (class "Default")
      (node (ref "PCB1") (pin "38") (pinfunction "PB-9_38") (pintype "unspecified"))
      (node (ref "PCB1") (pin "39") (pinfunction "PB-10_39") (pintype "unspecified"))
    )
    (net (code "74") (name "TRACK-3-1") (class "Default")
      (node (ref "B11") (pin "AC2") (pinfunction "AC2_AC2") (pintype "unspecified"))
      (node (ref "B13") (pin "AC2") (pinfunction "AC2_AC2") (pintype "unspecified"))
      (node (ref "B15") (pin "AC2") (pinfunction "AC2_AC2") (pintype "unspecified"))
      (node (ref "B9") (pin "AC2") (pinfunction "AC2_AC2") (pintype "unspecified"))
      (node (ref "PCB1") (pin "40") (pinfunction "PB-11_40") (pintype "unspecified"))
      (node (ref "PCB1") (pin "41") (pinfunction "PB-12_41") (pintype "unspecified"))
      (node (ref "R25") (pin "2") (pinfunction "2_2") (pintype "unspecified"))
      (node (ref "R29") (pin "2") (pinfunction "2_2") (pintype "unspecified"))
      (node (ref "R33") (pin "2") (pinfunction "2_2") (pintype "unspecified"))
      (node (ref "R37") (pin "2") (pinfunction "2_2") (pintype "unspecified"))
      (node (ref "U5") (pin "1") (pinfunction "1_1") (pintype "unspecified"))
      (node (ref "U5") (pin "3") (pinfunction "3_3") (pintype "unspecified"))
      (node (ref "U5") (pin "5") (pinfunction "5_5") (pintype "unspecified"))
      (node (ref "U5") (pin "7") (pinfunction "7_7") (pintype "unspecified"))
    )
    (net (code "75") (name "TRACK-3-2") (class "Default")
      (node (ref "PCB1") (pin "42") (pinfunction "PB-13_42") (pintype "unspecified"))
      (node (ref "PCB1") (pin "43") (pinfunction "PB-14_43") (pintype "unspecified"))
    )
    (net (code "76") (name "TRACK-4-1") (class "Default")
      (node (ref "B10") (pin "AC1") (pinfunction "AC1_AC1") (pintype "unspecified"))
      (node (ref "B12") (pin "AC1") (pinfunction "AC1_AC1") (pintype "unspecified"))
      (node (ref "B14") (pin "AC1") (pinfunction "AC1_AC1") (pintype "unspecified"))
      (node (ref "B16") (pin "AC1") (pinfunction "AC1_AC1") (pintype "unspecified"))
      (node (ref "PCB1") (pin "44") (pinfunction "PB-15_44") (pintype "unspecified"))
      (node (ref "PCB1") (pin "45") (pinfunction "PB-16_45") (pintype "unspecified"))
      (node (ref "R26") (pin "2") (pinfunction "2_2") (pintype "unspecified"))
      (node (ref "R30") (pin "2") (pinfunction "2_2") (pintype "unspecified"))
      (node (ref "R34") (pin "2") (pinfunction "2_2") (pintype "unspecified"))
      (node (ref "R38") (pin "2") (pinfunction "2_2") (pintype "unspecified"))
      (node (ref "U6") (pin "1") (pinfunction "1_1") (pintype "unspecified"))
      (node (ref "U6") (pin "3") (pinfunction "3_3") (pintype "unspecified"))
      (node (ref "U6") (pin "5") (pinfunction "5_5") (pintype "unspecified"))
      (node (ref "U6") (pin "7") (pinfunction "7_7") (pintype "unspecified"))
    )
    (net (code "77") (name "TRACK-4-2") (class "Default")
      (node (ref "PCB1") (pin "46") (pinfunction "PB-17_46") (pintype "unspecified"))
      (node (ref "PCB1") (pin "47") (pinfunction "PB-18_47") (pintype "unspecified"))
    )
    (net (code "78") (name "Track-1-2") (class "Default")
      (node (ref "H1") (pin "1") (pinfunction "1_1") (pintype "input"))
      (node (ref "H1") (pin "10") (pinfunction "10_10") (pintype "input"))
      (node (ref "H1") (pin "2") (pinfunction "2_2") (pintype "input"))
      (node (ref "H1") (pin "4") (pinfunction "4_4") (pintype "input"))
      (node (ref "H1") (pin "6") (pinfunction "6_6") (pintype "input"))
      (node (ref "H1") (pin "8") (pinfunction "8_8") (pintype "input"))
    )
    (net (code "79") (name "Track-2-2") (class "Default")
      (node (ref "H1") (pin "12") (pinfunction "12_12") (pintype "input"))
      (node (ref "H1") (pin "14") (pinfunction "14_14") (pintype "input"))
      (node (ref "H1") (pin "16") (pinfunction "16_16") (pintype "input"))
      (node (ref "H1") (pin "18") (pinfunction "18_18") (pintype "input"))
      (node (ref "H1") (pin "19") (pinfunction "19_19") (pintype "input"))
      (node (ref "H1") (pin "20") (pinfunction "20_20") (pintype "input"))
    )
    (net (code "80") (name "Track-3-2") (class "Default")
      (node (ref "H2") (pin "1") (pinfunction "1_1") (pintype "input"))
      (node (ref "H2") (pin "10") (pinfunction "10_10") (pintype "input"))
      (node (ref "H2") (pin "2") (pinfunction "2_2") (pintype "input"))
      (node (ref "H2") (pin "4") (pinfunction "4_4") (pintype "input"))
      (node (ref "H2") (pin "6") (pinfunction "6_6") (pintype "input"))
      (node (ref "H2") (pin "8") (pinfunction "8_8") (pintype "input"))
    )
    (net (code "81") (name "Track-4-2") (class "Default")
      (node (ref "H2") (pin "12") (pinfunction "12_12") (pintype "input"))
      (node (ref "H2") (pin "14") (pinfunction "14_14") (pintype "input"))
      (node (ref "H2") (pin "16") (pinfunction "16_16") (pintype "input"))
      (node (ref "H2") (pin "18") (pinfunction "18_18") (pintype "input"))
      (node (ref "H2") (pin "19") (pinfunction "19_19") (pintype "input"))
      (node (ref "H2") (pin "20") (pinfunction "20_20") (pintype "input"))
    )
    (net (code "82") (name "VCC") (class "Default")
      (node (ref "C1") (pin "2") (pinfunction "2_2") (pintype "unspecified"))
      (node (ref "C2") (pin "1") (pinfunction "1_1") (pintype "unspecified"))
      (node (ref "PCB1") (pin "90") (pinfunction "VCC_90") (pintype "unspecified"))
      (node (ref "PCB1") (pin "91") (pinfunction "VCC_91") (pintype "unspecified"))
      (node (ref "R17") (pin "2") (pinfunction "2_2") (pintype "unspecified"))
      (node (ref "R18") (pin "2") (pinfunction "2_2") (pintype "unspecified"))
      (node (ref "R19") (pin "2") (pinfunction "2_2") (pintype "unspecified"))
      (node (ref "R20") (pin "2") (pinfunction "2_2") (pintype "unspecified"))
      (node (ref "R21") (pin "2") (pinfunction "2_2") (pintype "unspecified"))
      (node (ref "R22") (pin "2") (pinfunction "2_2") (pintype "unspecified"))
      (node (ref "R23") (pin "2") (pinfunction "2_2") (pintype "unspecified"))
      (node (ref "R24") (pin "2") (pinfunction "2_2") (pintype "unspecified"))
      (node (ref "R41") (pin "2") (pinfunction "2_2") (pintype "unspecified"))
      (node (ref "R42") (pin "2") (pinfunction "2_2") (pintype "unspecified"))
      (node (ref "R43") (pin "2") (pinfunction "2_2") (pintype "unspecified"))
      (node (ref "R44") (pin "2") (pinfunction "2_2") (pintype "unspecified"))
      (node (ref "R45") (pin "2") (pinfunction "2_2") (pintype "unspecified"))
      (node (ref "R46") (pin "2") (pinfunction "2_2") (pintype "unspecified"))
      (node (ref "R47") (pin "2") (pinfunction "2_2") (pintype "unspecified"))
      (node (ref "R48") (pin "2") (pinfunction "2_2") (pintype "unspecified"))
      (node (ref "U1") (pin "7") (pinfunction "WP_7") (pintype "unspecified"))
      (node (ref "U1") (pin "8") (pinfunction "VCC_8") (pintype "unspecified"))
      (node (ref "U2") (pin "24") (pinfunction "VDD_24") (pintype "unspecified"))
    )
    (net (code "83") (name "unconnected-(PCB1-ADC-0-Pad64)") (class "Default")
      (node (ref "PCB1") (pin "64") (pinfunction "ADC-0_64") (pintype "unspecified+no_connect"))
    )
    (net (code "84") (name "unconnected-(PCB1-ADC-1-Pad65)") (class "Default")
      (node (ref "PCB1") (pin "65") (pinfunction "ADC-1_65") (pintype "unspecified+no_connect"))
    )
    (net (code "85") (name "unconnected-(PCB1-BC-2-Pad84)") (class "Default")
      (node (ref "PCB1") (pin "84") (pinfunction "BC-2_84") (pintype "unspecified+no_connect"))
    )
    (net (code "86") (name "unconnected-(PCB1-BC-3-Pad85)") (class "Default")
      (node (ref "PCB1") (pin "85") (pinfunction "BC-3_85") (pintype "unspecified+no_connect"))
    )
    (net (code "87") (name "unconnected-(PCB1-DCC-1-Pad60)") (class "Default")
      (node (ref "PCB1") (pin "60") (pinfunction "DCC-1_60") (pintype "unspecified+no_connect"))
    )
    (net (code "88") (name "unconnected-(PCB1-DCC-2-Pad61)") (class "Default")
      (node (ref "PCB1") (pin "61") (pinfunction "DCC-2_61") (pintype "unspecified+no_connect"))
    )
    (net (code "89") (name "unconnected-(PCB1-DIO-0-Pad68)") (class "Default")
      (node (ref "PCB1") (pin "68") (pinfunction "DIO-0_68") (pintype "unspecified+no_connect"))
    )
    (net (code "90") (name "unconnected-(PCB1-DIO-1-Pad19)") (class "Default")
      (node (ref "PCB1") (pin "19") (pinfunction "DIO-1_19") (pintype "unspecified+no_connect"))
    )
    (net (code "91") (name "unconnected-(PCB1-DIO-2-Pad70)") (class "Default")
      (node (ref "PCB1") (pin "70") (pinfunction "DIO-2_70") (pintype "unspecified+no_connect"))
    )
    (net (code "92") (name "unconnected-(PCB1-DIO-3-Pad71)") (class "Default")
      (node (ref "PCB1") (pin "71") (pinfunction "DIO-3_71") (pintype "unspecified+no_connect"))
    )
    (net (code "93") (name "unconnected-(PCB1-DIO-4-Pad72)") (class "Default")
      (node (ref "PCB1") (pin "72") (pinfunction "DIO-4_72") (pintype "unspecified+no_connect"))
    )
    (net (code "94") (name "unconnected-(PCB1-DIO-5-Pad73)") (class "Default")
      (node (ref "PCB1") (pin "73") (pinfunction "DIO-5_73") (pintype "unspecified+no_connect"))
    )
    (net (code "95") (name "unconnected-(PCB1-DIO-6-Pad74)") (class "Default")
      (node (ref "PCB1") (pin "74") (pinfunction "DIO-6_74") (pintype "unspecified+no_connect"))
    )
    (net (code "96") (name "unconnected-(PCB1-DIO-7-Pad75)") (class "Default")
      (node (ref "PCB1") (pin "75") (pinfunction "DIO-7_75") (pintype "unspecified+no_connect"))
    )
    (net (code "97") (name "unconnected-(PCB1-DIO-8-Pad76)") (class "Default")
      (node (ref "PCB1") (pin "76") (pinfunction "DIO-8_76") (pintype "unspecified+no_connect"))
    )
    (net (code "98") (name "unconnected-(PCB1-DIO-9-Pad77)") (class "Default")
      (node (ref "PCB1") (pin "77") (pinfunction "DIO-9_77") (pintype "unspecified+no_connect"))
    )
    (net (code "99") (name "unconnected-(PCB1-DIO-10-Pad78)") (class "Default")
      (node (ref "PCB1") (pin "78") (pinfunction "DIO-10_78") (pintype "unspecified+no_connect"))
    )
    (net (code "100") (name "unconnected-(PCB1-DIO-11-Pad79)") (class "Default")
      (node (ref "PCB1") (pin "79") (pinfunction "DIO-11_79") (pintype "unspecified+no_connect"))
    )
    (net (code "101") (name "unconnected-(PCB1-EXT-Pad89)") (class "Default")
      (node (ref "PCB1") (pin "89") (pinfunction "EXT_89") (pintype "unspecified+no_connect"))
    )
    (net (code "102") (name "unconnected-(PCB1-GND-Pad66)") (class "Default")
      (node (ref "PCB1") (pin "66") (pinfunction "GND_66") (pintype "unspecified+no_connect"))
    )
    (net (code "103") (name "unconnected-(PCB1-GND-Pad67)") (class "Default")
      (node (ref "PCB1") (pin "67") (pinfunction "GND_67") (pintype "unspecified+no_connect"))
    )
    (net (code "104") (name "unconnected-(PCB1-RST-Pad88)") (class "Default")
      (node (ref "PCB1") (pin "88") (pinfunction "RST_88") (pintype "unspecified+no_connect"))
    )
    (net (code "105") (name "unconnected-(PCB1-VS-Pad94)") (class "Default")
      (node (ref "PCB1") (pin "94") (pinfunction "VS_94") (pintype "unspecified+no_connect"))
    )
    (net (code "106") (name "unconnected-(PCB1-VS-Pad95)") (class "Default")
      (node (ref "PCB1") (pin "95") (pinfunction "VS_95") (pintype "unspecified+no_connect"))
    )
    (net (code "107") (name "unconnected-(PCB1-VS-Pad96)") (class "Default")
      (node (ref "PCB1") (pin "96") (pinfunction "VS_96") (pintype "unspecified+no_connect"))
    )
    (net (code "108") (name "unconnected-(PCB1-VS-Pad97)") (class "Default")
      (node (ref "PCB1") (pin "97") (pinfunction "VS_97") (pintype "unspecified+no_connect"))
    )
    (net (code "109") (name "unconnected-(U2-INT#-Pad1)") (class "Default")
      (node (ref "U2") (pin "1") (pinfunction "INT#_1") (pintype "unspecified+no_connect"))
    )
  )
)
